# CH32F203C8T6-R1.net
KiCad netlist of a schematic drawn in Altium Designer
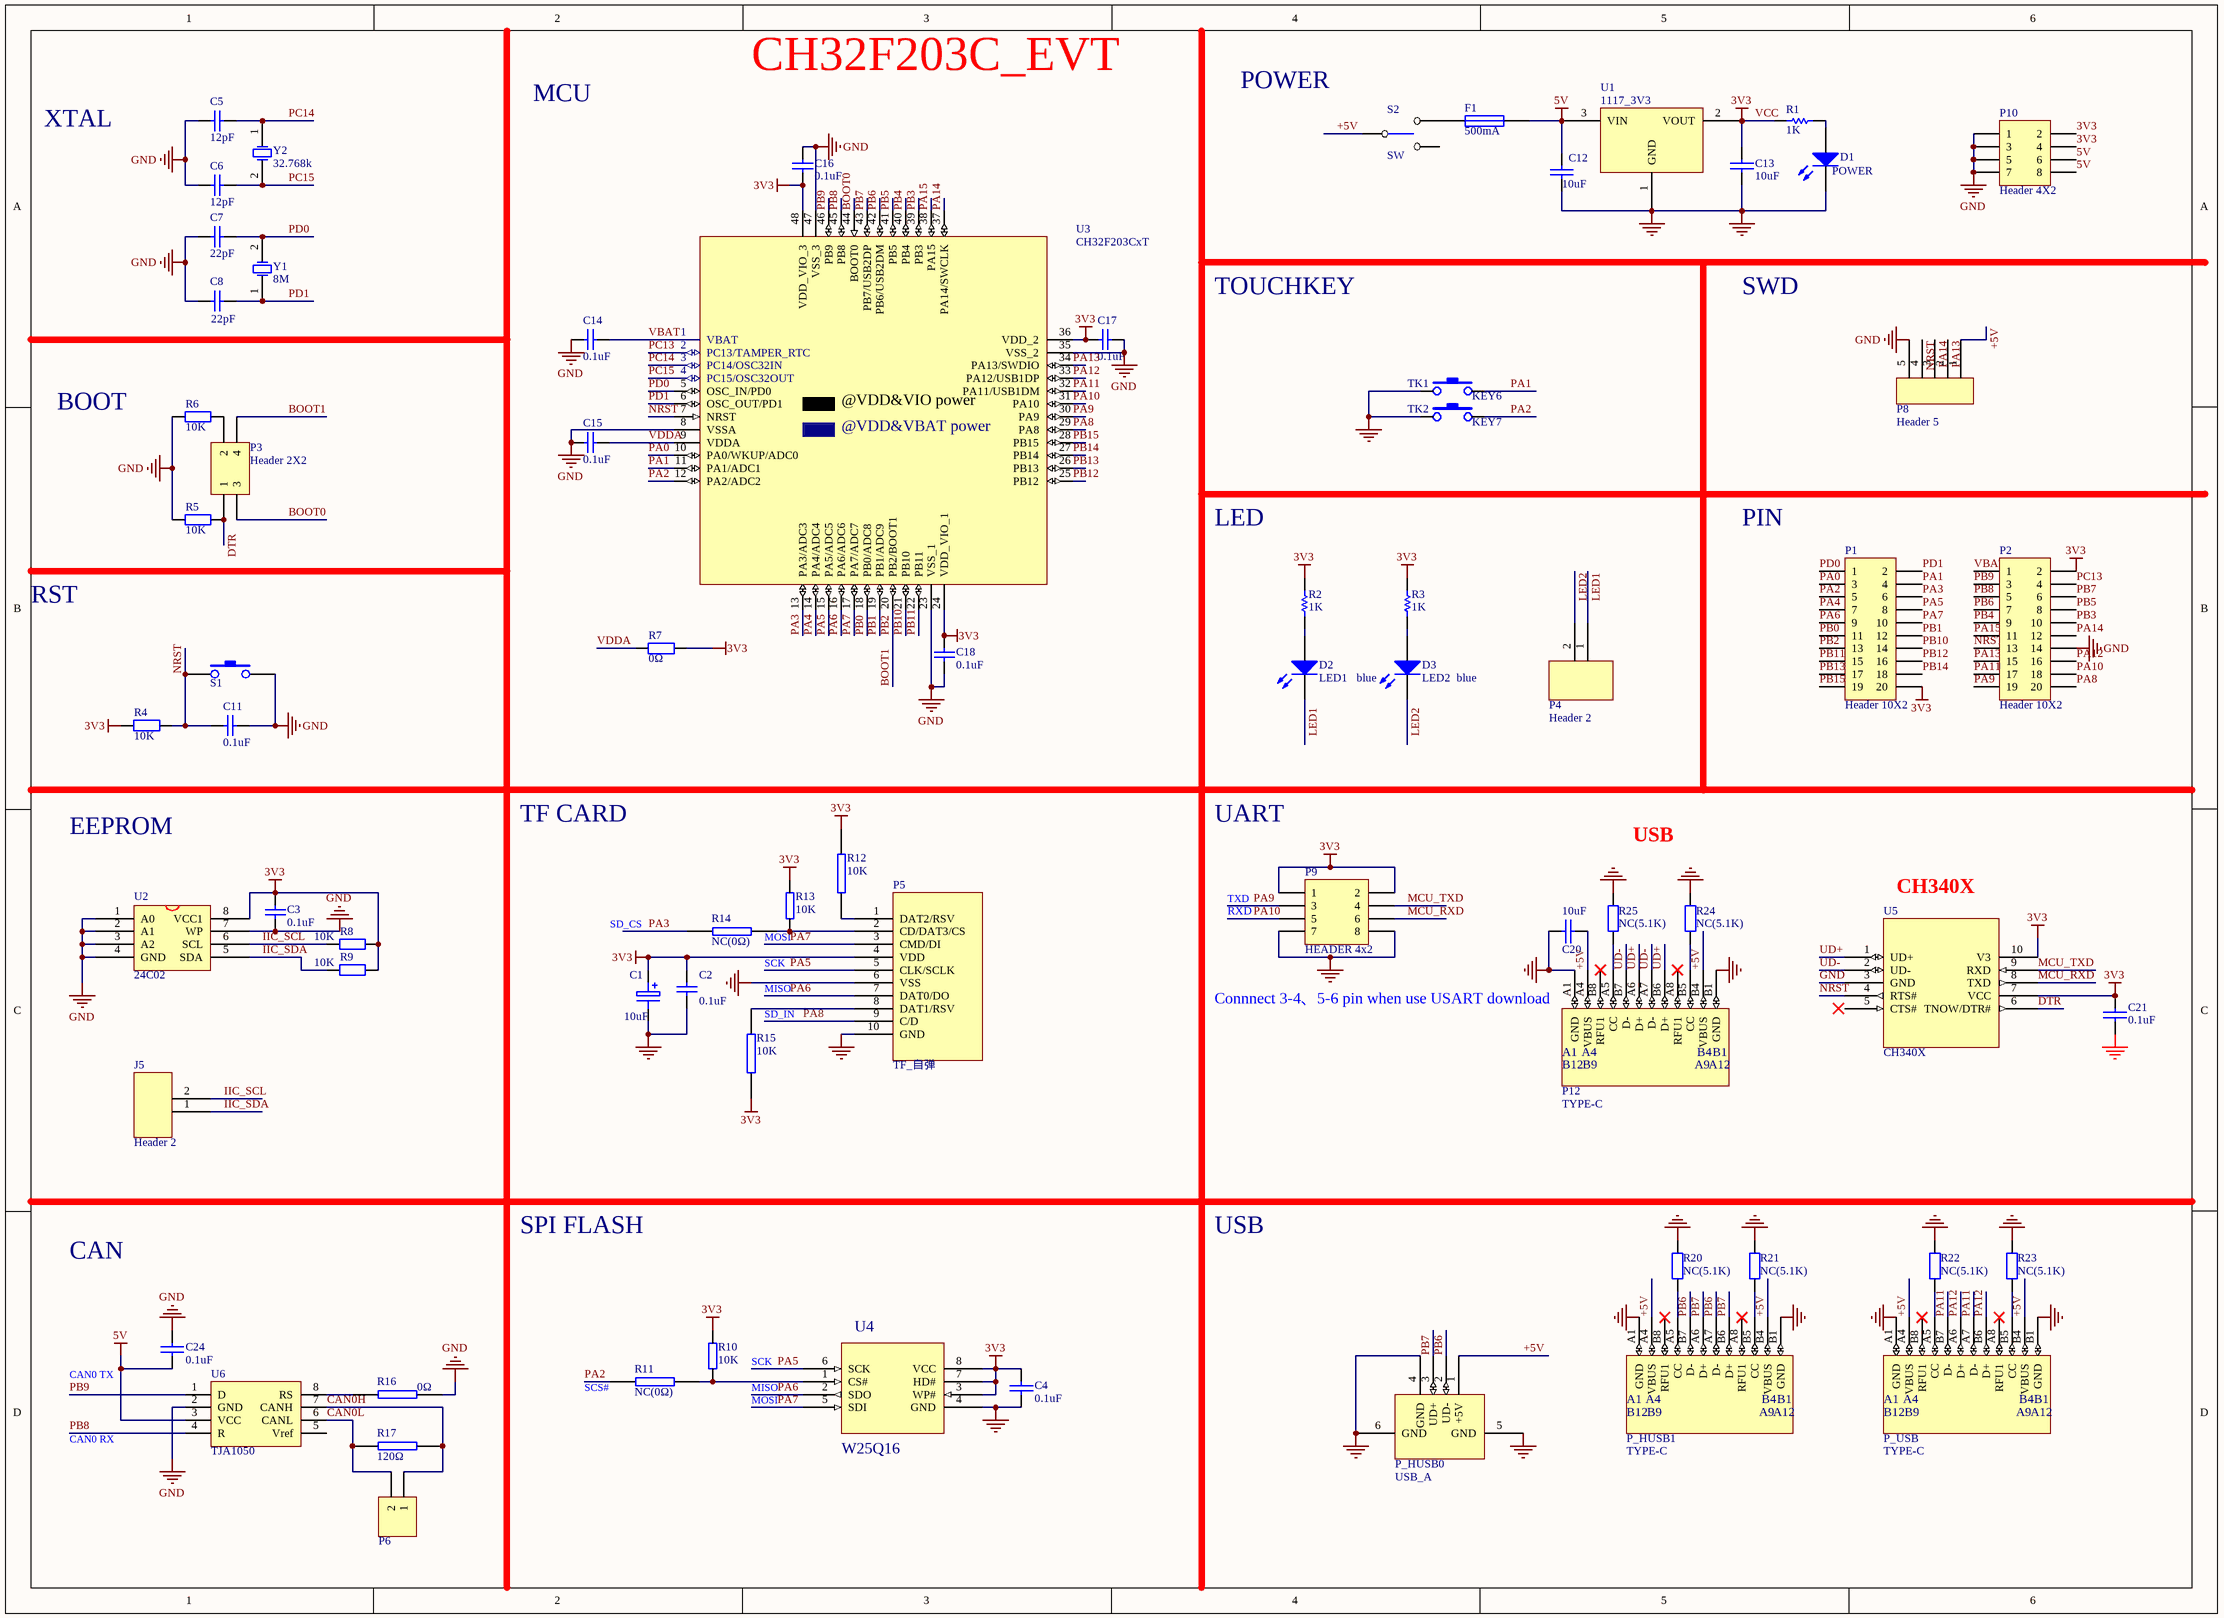
[diagram p0: CH32F203C8T6-R1.SchDoc]

(export (version "E")
  (design (tool "Eeschema 10.0.6"))
  (components
    (comp (ref "C1")
      (value "10uF")
      (footprint "3216")
      (description "Electrolytic Capacitor")
      (libsource (lib "*") (part "ELECTRO1"))
    )
    (comp (ref "C2")
      (value "0.1uF")
      (footprint "0603")
      (description "Capacitor")
      (fields (field (name "PUBLISHER") "Altium Limited"))
      (libsource (lib "*") (part "Cap"))
    )
    (comp (ref "C3")
      (value "0.1uF")
      (footprint "0603")
      (description "Capacitor")
      (fields (field (name "PUBLISHER") "Altium Limited"))
      (libsource (lib "Miscellaneous Devices") (part "Cap"))
    )
    (comp (ref "C4")
      (value "0.1uF")
      (footprint "0603")
      (description "Capacitor")
      (libsource (lib "") (part "CAP_1"))
    )
    (comp (ref "C5")
      (value "12pF")
      (footprint "0603")
      (description "Capacitor")
      (fields (field (name "PUBLISHER") "Altium Limited"))
      (libsource (lib "Miscellaneous Devices") (part "Cap"))
    )
    (comp (ref "C6")
      (value "12pF")
      (footprint "0603")
      (description "Capacitor")
      (fields (field (name "PUBLISHER") "Altium Limited"))
      (libsource (lib "Miscellaneous Devices") (part "Cap"))
    )
    (comp (ref "C7")
      (value "22pF")
      (footprint "0603")
      (description "Capacitor")
      (fields (field (name "PUBLISHER") "Altium Limited"))
      (libsource (lib "Miscellaneous Devices") (part "Cap"))
    )
    (comp (ref "C8")
      (value "22pF")
      (footprint "0603")
      (description "Capacitor")
      (fields (field (name "PUBLISHER") "Altium Limited"))
      (libsource (lib "Miscellaneous Devices") (part "Cap"))
    )
    (comp (ref "C11")
      (value "0.1uF")
      (footprint "0603")
      (description "Capacitor")
      (fields (field (name "PUBLISHER") "Altium Limited"))
      (libsource (lib "Miscellaneous Devices") (part "Cap"))
    )
    (comp (ref "C12")
      (value "10uF")
      (footprint "3216")
      (description "Capacitor")
      (libsource (lib "*") (part "CAP"))
    )
    (comp (ref "C13")
      (value "10uF")
      (footprint "0603")
      (description "Capacitor")
      (libsource (lib "*") (part "CAP"))
    )
    (comp (ref "C14")
      (value "0.1uF")
      (footprint "0603")
      (description "Capacitor")
      (fields (field (name "PUBLISHER") "Altium Limited"))
      (libsource (lib "Miscellaneous Devices") (part "Cap"))
    )
    (comp (ref "C15")
      (value "0.1uF")
      (footprint "0603")
      (description "Capacitor")
      (fields (field (name "PUBLISHER") "Altium Limited"))
      (libsource (lib "Miscellaneous Devices") (part "Cap"))
    )
    (comp (ref "C16")
      (value "0.1uF")
      (footprint "0603")
      (description "Capacitor")
      (fields (field (name "PUBLISHER") "Altium Limited"))
      (libsource (lib "Miscellaneous Devices") (part "Cap"))
    )
    (comp (ref "C17")
      (value "0.1uF")
      (footprint "0603")
      (description "Capacitor")
      (fields (field (name "PUBLISHER") "Altium Limited"))
      (libsource (lib "Miscellaneous Devices") (part "Cap"))
    )
    (comp (ref "C18")
      (value "0.1uF")
      (footprint "0603")
      (description "Capacitor")
      (fields (field (name "PUBLISHER") "Altium Limited"))
      (libsource (lib "Miscellaneous Devices") (part "Cap"))
    )
    (comp (ref "C20")
      (value "10uF")
      (footprint "3216_C")
      (description "Capacitor")
      (libsource (lib "*") (part "CAP"))
    )
    (comp (ref "C21")
      (value "0.1uF")
      (footprint "0603_C")
      (description "Capacitor")
      (libsource (lib "*") (part "CAP"))
    )
    (comp (ref "C24")
      (value "0.1uF")
      (footprint "0603")
      (description "Capacitor")
      (libsource (lib "") (part "CAP_1"))
    )
    (comp (ref "D1")
      (value "POWER")
      (footprint "0603L")
      (description "Typical INFRARED GaAs LED")
      (fields (field (name "PUBLISHER") "Altium Limited"))
      (libsource (lib "Miscellaneous Devices") (part "LED0"))
    )
    (comp (ref "D2")
      (value "LED1   blue")
      (footprint "0603L")
      (description "Typical INFRARED GaAs LED")
      (fields (field (name "PUBLISHER") "Altium Limited"))
      (libsource (lib "Miscellaneous Devices") (part "LED0"))
    )
    (comp (ref "D3")
      (value "LED2  blue")
      (footprint "0603L")
      (description "Typical INFRARED GaAs LED")
      (fields (field (name "PUBLISHER") "Altium Limited"))
      (libsource (lib "Miscellaneous Devices") (part "LED0"))
    )
    (comp (ref "F1")
      (value "500mA")
      (footprint "0603")
      (description "Fuse")
      (libsource (lib "*") (part "FUSE1"))
    )
    (comp (ref "J5") (value "Header 2") (footprint "SIP2 - 40mil") (libsource (lib "MYSCH") (part "2HEAD")))
    (comp (ref "P1")
      (value "Header 10X2")
      (footprint "IDC20")
      (description "Header, 10-Pin, Dual row")
      (fields (field (name "PUBLISHER") "Altium Limited"))
      (libsource (lib "Miscellaneous Connectors") (part "Header 10X2"))
    )
    (comp (ref "P2")
      (value "Header 10X2")
      (footprint "IDC20")
      (description "Header, 10-Pin, Dual row")
      (fields (field (name "PUBLISHER") "Altium Limited"))
      (libsource (lib "Miscellaneous Connectors") (part "Header 10X2"))
    )
    (comp (ref "P3")
      (value "Header 2X2")
      (footprint "HDR2X2")
      (description "Header, 2-Pin, Dual row")
      (fields (field (name "PUBLISHER") "Altium Limited"))
      (libsource (lib "Miscellaneous Connectors") (part "Header 2X2"))
    )
    (comp (ref "P4") (value "Header 2") (footprint "SIP2 - 40mil") (libsource (lib "") (part "2HEAD_1")))
    (comp (ref "P5") (value "TF_自弹") (footprint "TF_CARD") (libsource (lib "*") (part "TF_自弹")))
    (comp (ref "P6")
      (value "Header 2")
      (footprint "PORT2 4.5MM")
      (description "Header, 2-Pin")
      (fields (field (name "PUBLISHER") "Altium Limited"))
      (libsource (lib "Miscellaneous Connectors") (part "Header 2"))
    )
    (comp (ref "P8")
      (value "Header 5")
      (footprint "SIP5 - 40mil")
      (libsource (lib "PCB_Project1") (part "2HEAD"))
    )
    (comp (ref "P9")
      (value "HEADER 4x2")
      (footprint "MYPCB:IDC8-2.54mm")
      (description "Header, 4-Pin, Dual row")
      (libsource (lib "wch_sch_others") (part "HEADER 4x2"))
    )
    (comp (ref "P10")
      (value "Header 4X2")
      (footprint "IDC8")
      (description "Header, 4-Pin, Dual row")
      (fields (field (name "PUBLISHER") "Altium Limited"))
      (libsource (lib "Miscellaneous Connectors") (part "Header 4X2"))
    )
    (comp (ref "P12")
      (value "TYPE-C")
      (footprint "TYPE-C-Receptacle-2.0")
      (libsource (lib "*") (part "TYPE-C1"))
    )
    (comp (ref "P_HUSB0")
      (value "USB_A")
      (footprint "USBA-l")
      (description "USB Port")
      (libsource (lib "CHXXXSCH") (part "USB"))
    )
    (comp (ref "P_HUSB1")
      (value "TYPE-C")
      (footprint "TYPE-C-Receptacle-2.0")
      (libsource (lib "*") (part "TYPE-C1"))
    )
    (comp (ref "P_USB")
      (value "TYPE-C")
      (footprint "TYPE-C-Receptacle-2.0")
      (libsource (lib "*") (part "TYPE-C1"))
    )
    (comp (ref "R1")
      (value "1K")
      (footprint "0603")
      (description "Semiconductor Resistor")
      (fields (field (name "PUBLISHER") "Altium Limited"))
      (libsource (lib "Miscellaneous Devices") (part "Res Semi"))
    )
    (comp (ref "R2")
      (value "1K")
      (footprint "0603")
      (description "Semiconductor Resistor")
      (fields (field (name "PUBLISHER") "Altium Limited"))
      (libsource (lib "Miscellaneous Devices") (part "Res Semi"))
    )
    (comp (ref "R3")
      (value "1K")
      (footprint "0603")
      (description "Semiconductor Resistor")
      (fields (field (name "PUBLISHER") "Altium Limited"))
      (libsource (lib "Miscellaneous Devices") (part "Res Semi"))
    )
    (comp (ref "R4")
      (value "10K")
      (footprint "0603")
      (description "Resistor")
      (fields (field (name "PUBLISHER") "Altium Limited"))
      (libsource (lib "") (part "Res2_1"))
    )
    (comp (ref "R5")
      (value "10K")
      (footprint "0603")
      (description "Resistor")
      (fields (field (name "PUBLISHER") "Altium Limited"))
      (libsource (lib "") (part "Res2_1"))
    )
    (comp (ref "R6")
      (value "10K")
      (footprint "0603")
      (description "Resistor")
      (fields (field (name "PUBLISHER") "Altium Limited"))
      (libsource (lib "") (part "Res2_1"))
    )
    (comp (ref "R7")
      (value "0Ω")
      (footprint "0603")
      (description "Resistor")
      (fields (field (name "PUBLISHER") "Altium Limited"))
      (libsource (lib "") (part "Res2_1"))
    )
    (comp (ref "R8")
      (value "10K")
      (footprint "0603")
      (description "Resistor")
      (fields (field (name "PUBLISHER") "Altium Limited"))
      (libsource (lib "") (part "Res2_1"))
    )
    (comp (ref "R9")
      (value "10K")
      (footprint "0603")
      (description "Resistor")
      (fields (field (name "PUBLISHER") "Altium Limited"))
      (libsource (lib "") (part "Res2_1"))
    )
    (comp (ref "R10") (value "10K") (footprint "0603") (libsource (lib "*") (part "DZ")))
    (comp (ref "R11") (value "NC(0Ω)") (footprint "0603") (libsource (lib "*") (part "RES2")))
    (comp (ref "R12") (value "10K") (footprint "0603") (libsource (lib "*") (part "RES2")))
    (comp (ref "R13") (value "10K") (footprint "0603") (libsource (lib "*") (part "DZ")))
    (comp (ref "R14") (value "NC(0Ω)") (footprint "0603") (libsource (lib "*") (part "RES2")))
    (comp (ref "R15") (value "10K") (footprint "0603") (libsource (lib "*") (part "RES2")))
    (comp (ref "R16") (value "0Ω") (footprint "0603") (libsource (lib "*") (part "RES2")))
    (comp (ref "R17") (value "120Ω") (footprint "0603") (libsource (lib "*") (part "RES2")))
    (comp (ref "R20")
      (value "NC(5.1K)")
      (footprint "0603")
      (description "Resistor")
      (libsource (lib "Miscellaneous Devices") (part "Res2"))
    )
    (comp (ref "R21")
      (value "NC(5.1K)")
      (footprint "0603")
      (description "Resistor")
      (libsource (lib "Miscellaneous Devices") (part "Res2"))
    )
    (comp (ref "R22")
      (value "NC(5.1K)")
      (footprint "0603")
      (description "Resistor")
      (libsource (lib "Miscellaneous Devices") (part "Res2"))
    )
    (comp (ref "R23")
      (value "NC(5.1K)")
      (footprint "0603")
      (description "Resistor")
      (libsource (lib "Miscellaneous Devices") (part "Res2"))
    )
    (comp (ref "R24")
      (value "NC(5.1K)")
      (footprint "0603")
      (description "Resistor")
      (libsource (lib "Miscellaneous Devices") (part "Res2"))
    )
    (comp (ref "R25")
      (value "NC(5.1K)")
      (footprint "0603")
      (description "Resistor")
      (libsource (lib "Miscellaneous Devices") (part "Res2"))
    )
    (comp (ref "S1") (value "KEY") (footprint "贴片按键") (libsource (lib "CCDXPLIB") (part "KEY")))
    (comp (ref "S2") (value "SW") (footprint "KEY2") (libsource (lib "MYSCH") (part "SW")))
    (comp (ref "TK1") (value "KEY6") (footprint "KEY68") (libsource (lib "*") (part "KEY")))
    (comp (ref "TK2") (value "KEY7") (footprint "KEY68") (libsource (lib "*") (part "KEY")))
    (comp (ref "U1") (value "1117_3V3") (footprint "SOT-223") (libsource (lib "*") (part "LM1117_3.3V")))
    (comp (ref "U2") (value "24C02") (footprint "SOP8") (libsource (lib "Elite_SCH") (part "24C256")))
    (comp (ref "U3")
      (value "CH32F203CxT")
      (footprint "LQFP48")
      (description "ARM M3 LMD-MCU, 144MHz, 2*USB FS, CAN")
      (libsource (lib "CHXXX") (part "CH32F203CxT"))
    )
    (comp (ref "U4")
      (value "W25Q16")
      (footprint "016 SO-8")
      (libsource (lib "*") (part "Pro89C.tmp_25F512_2"))
    )
    (comp (ref "U5")
      (value "CH340X")
      (footprint "MSOP10")
      (description "USB to TTL Serial / UART")
      (libsource (lib "CHXXX") (part "CH340X"))
    )
    (comp (ref "U6") (value "TJA1050") (footprint "SOP8") (libsource (lib "CAN") (part "Component_1")))
    (comp (ref "Y1")
      (value "8M")
      (footprint "XT62/28")
      (description "Crystal Oscillator")
      (fields (field (name "PUBLISHER") "Altium Limited"))
      (libsource (lib "Miscellaneous Devices") (part "XTAL"))
    )
    (comp (ref "Y2")
      (value "32.768k")
      (footprint "FC-135")
      (description "Crystal Oscillator")
      (fields (field (name "PUBLISHER") "Altium Limited"))
      (libsource (lib "Miscellaneous Devices") (part "XTAL"))
    )
  )
  (nets
    (net (code "1") (name "/+5V") (class "Default")
      (node (ref "C20") (pin "2") (pinfunction "2_2") (pintype "passive"))
      (node (ref "P12") (pin "A4") (pinfunction "VBUS_A4") (pintype "bidirectional"))
      (node (ref "P12") (pin "B4") (pinfunction "VBUS_B4") (pintype "bidirectional"))
      (node (ref "P8") (pin "1") (pintype "passive"))
      (node (ref "P_HUSB0") (pin "1") (pinfunction "+5V_1") (pintype "power_in"))
      (node (ref "P_HUSB1") (pin "A4") (pinfunction "VBUS_A4") (pintype "bidirectional"))
      (node (ref "P_HUSB1") (pin "B4") (pinfunction "VBUS_B4") (pintype "bidirectional"))
      (node (ref "P_USB") (pin "A4") (pinfunction "VBUS_A4") (pintype "bidirectional"))
      (node (ref "P_USB") (pin "B4") (pinfunction "VBUS_B4") (pintype "bidirectional"))
      (node (ref "S2") (pin "1") (pinfunction "1_1") (pintype "passive"))
    )
    (net (code "3") (name "/BOOT0") (class "Default")
      (node (ref "P3") (pin "3") (pinfunction "3_3") (pintype "passive"))
      (node (ref "U3") (pin "44") (pinfunction "BOOT0_44") (pintype "input"))
    )
    (net (code "4") (name "/BOOT1") (class "Default")
      (node (ref "P1") (pin "13") (pinfunction "13_13") (pintype "passive"))
      (node (ref "P3") (pin "4") (pinfunction "4_4") (pintype "passive"))
      (node (ref "U3") (pin "20") (pinfunction "PB2/BOOT1_20") (pintype "bidirectional"))
    )
    (net (code "5") (name "/CAN0H") (class "Default")
      (node (ref "P6") (pin "1") (pinfunction "1_1") (pintype "passive"))
      (node (ref "R17") (pin "1") (pinfunction "1_1") (pintype "passive"))
      (node (ref "U6") (pin "7") (pinfunction "CANH_7") (pintype "passive"))
    )
    (net (code "6") (name "/CAN0L") (class "Default")
      (node (ref "P6") (pin "2") (pinfunction "2_2") (pintype "passive"))
      (node (ref "R17") (pin "2") (pinfunction "2_2") (pintype "passive"))
      (node (ref "U6") (pin "6") (pinfunction "CANL_6") (pintype "passive"))
    )
    (net (code "7") (name "/DTR") (class "Default")
      (node (ref "P3") (pin "1") (pinfunction "1_1") (pintype "passive"))
      (node (ref "R5") (pin "1") (pinfunction "1_1") (pintype "passive"))
      (node (ref "U5") (pin "6") (pinfunction "TNOW/DTR#_6") (pintype "output"))
    )
    (net (code "8") (name "/IIC_SCL") (class "Default")
      (node (ref "J5") (pin "2") (pintype "passive"))
      (node (ref "R8") (pin "2") (pinfunction "2_2") (pintype "passive"))
      (node (ref "U2") (pin "6") (pinfunction "SCL_6") (pintype "passive"))
    )
    (net (code "9") (name "/IIC_SDA") (class "Default")
      (node (ref "J5") (pin "1") (pintype "passive"))
      (node (ref "R9") (pin "2") (pinfunction "2_2") (pintype "passive"))
      (node (ref "U2") (pin "5") (pinfunction "SDA_5") (pintype "passive"))
    )
    (net (code "10") (name "/LED1") (class "Default")
      (node (ref "D2") (pin "2") (pinfunction "K_2") (pintype "passive"))
      (node (ref "P4") (pin "1") (pintype "passive"))
    )
    (net (code "11") (name "/LED2") (class "Default")
      (node (ref "D3") (pin "2") (pinfunction "K_2") (pintype "passive"))
      (node (ref "P4") (pin "2") (pintype "passive"))
    )
    (net (code "12") (name "/MCU_RXD") (class "Default")
      (node (ref "P9") (pin "6") (pinfunction "6_6") (pintype "passive"))
      (node (ref "U5") (pin "8") (pinfunction "TXD_8") (pintype "output"))
    )
    (net (code "13") (name "/MCU_TXD") (class "Default")
      (node (ref "P9") (pin "4") (pinfunction "4_4") (pintype "passive"))
      (node (ref "U5") (pin "9") (pinfunction "RXD_9") (pintype "input"))
    )
    (net (code "14") (name "/NRST") (class "Default")
      (node (ref "C11") (pin "2") (pinfunction "2_2") (pintype "passive"))
      (node (ref "P2") (pin "13") (pinfunction "13_13") (pintype "passive"))
      (node (ref "P8") (pin "4") (pintype "passive"))
      (node (ref "R4") (pin "1") (pinfunction "1_1") (pintype "passive"))
      (node (ref "S1") (pin "1") (pinfunction "1_1") (pintype "passive"))
      (node (ref "U3") (pin "7") (pinfunction "NRST_7") (pintype "input"))
      (node (ref "U5") (pin "4") (pinfunction "RTS#_4") (pintype "output"))
    )
    (net (code "15") (name "/PA0") (class "Default")
      (node (ref "P1") (pin "3") (pinfunction "3_3") (pintype "passive"))
      (node (ref "U3") (pin "10") (pinfunction "PA0/WKUP/ADC0_10") (pintype "bidirectional"))
    )
    (net (code "16") (name "/PA1") (class "Default")
      (node (ref "P1") (pin "4") (pinfunction "4_4") (pintype "passive"))
      (node (ref "TK1") (pin "1") (pintype "passive"))
      (node (ref "U3") (pin "11") (pinfunction "PA1/ADC1_11") (pintype "bidirectional"))
    )
    (net (code "17") (name "/PA2") (class "Default")
      (node (ref "P1") (pin "5") (pinfunction "5_5") (pintype "passive"))
      (node (ref "R11") (pin "2") (pinfunction "2_2") (pintype "passive"))
      (node (ref "TK2") (pin "1") (pintype "passive"))
      (node (ref "U3") (pin "12") (pinfunction "PA2/ADC2_12") (pintype "bidirectional"))
    )
    (net (code "18") (name "/PA3") (class "Default")
      (node (ref "P1") (pin "6") (pinfunction "6_6") (pintype "passive"))
      (node (ref "R14") (pin "2") (pinfunction "2_2") (pintype "passive"))
      (node (ref "U3") (pin "13") (pinfunction "PA3/ADC3_13") (pintype "bidirectional"))
    )
    (net (code "19") (name "/PA4") (class "Default")
      (node (ref "P1") (pin "7") (pinfunction "7_7") (pintype "passive"))
      (node (ref "U3") (pin "14") (pinfunction "PA4/ADC4_14") (pintype "bidirectional"))
    )
    (net (code "20") (name "/PA5") (class "Default")
      (node (ref "P1") (pin "8") (pinfunction "8_8") (pintype "passive"))
      (node (ref "P5") (pin "5") (pinfunction "CLK/SCLK_5") (pintype "passive"))
      (node (ref "U3") (pin "15") (pinfunction "PA5/ADC5_15") (pintype "bidirectional"))
      (node (ref "U4") (pin "6") (pinfunction "SCK_6") (pintype "input"))
    )
    (net (code "21") (name "/PA6") (class "Default")
      (node (ref "P1") (pin "9") (pinfunction "9_9") (pintype "passive"))
      (node (ref "P5") (pin "7") (pinfunction "DAT0/DO_7") (pintype "passive"))
      (node (ref "U3") (pin "16") (pinfunction "PA6/ADC6_16") (pintype "bidirectional"))
      (node (ref "U4") (pin "2") (pinfunction "SDO_2") (pintype "output"))
    )
    (net (code "22") (name "/PA7") (class "Default")
      (node (ref "P1") (pin "10") (pinfunction "10_10") (pintype "passive"))
      (node (ref "P5") (pin "3") (pinfunction "CMD/DI_3") (pintype "passive"))
      (node (ref "U3") (pin "17") (pinfunction "PA7/ADC7_17") (pintype "bidirectional"))
      (node (ref "U4") (pin "5") (pinfunction "SDI_5") (pintype "input"))
    )
    (net (code "23") (name "/PA8") (class "Default")
      (node (ref "P2") (pin "20") (pinfunction "20_20") (pintype "passive"))
      (node (ref "P5") (pin "9") (pinfunction "C/D_9") (pintype "passive"))
      (node (ref "U3") (pin "29") (pinfunction "PA8_29") (pintype "bidirectional"))
    )
    (net (code "24") (name "/PA9") (class "Default")
      (node (ref "P2") (pin "19") (pinfunction "19_19") (pintype "passive"))
      (node (ref "P9") (pin "3") (pinfunction "3_3") (pintype "passive"))
      (node (ref "U3") (pin "30") (pinfunction "PA9_30") (pintype "bidirectional"))
    )
    (net (code "25") (name "/PA10") (class "Default")
      (node (ref "P2") (pin "18") (pinfunction "18_18") (pintype "passive"))
      (node (ref "P9") (pin "5") (pinfunction "5_5") (pintype "passive"))
      (node (ref "U3") (pin "31") (pinfunction "PA10_31") (pintype "bidirectional"))
    )
    (net (code "26") (name "/PA11") (class "Default")
      (node (ref "P2") (pin "17") (pinfunction "17_17") (pintype "passive"))
      (node (ref "P_USB") (pin "A7") (pinfunction "D-_A7") (pintype "bidirectional"))
      (node (ref "P_USB") (pin "B7") (pinfunction "D-_B7") (pintype "bidirectional"))
      (node (ref "U3") (pin "32") (pinfunction "PA11/USB1DM_32") (pintype "bidirectional"))
    )
    (net (code "27") (name "/PA12") (class "Default")
      (node (ref "P2") (pin "16") (pinfunction "16_16") (pintype "passive"))
      (node (ref "P_USB") (pin "A6") (pinfunction "D+_A6") (pintype "bidirectional"))
      (node (ref "P_USB") (pin "B6") (pinfunction "D+_B6") (pintype "bidirectional"))
      (node (ref "U3") (pin "33") (pinfunction "PA12/USB1DP_33") (pintype "bidirectional"))
    )
    (net (code "28") (name "/PA13") (class "Default")
      (node (ref "P2") (pin "15") (pinfunction "15_15") (pintype "passive"))
      (node (ref "P8") (pin "2") (pintype "passive"))
      (node (ref "U3") (pin "34") (pinfunction "PA13/SWDIO_34") (pintype "bidirectional"))
    )
    (net (code "29") (name "/PA14") (class "Default")
      (node (ref "P2") (pin "12") (pinfunction "12_12") (pintype "passive"))
      (node (ref "P8") (pin "3") (pintype "passive"))
      (node (ref "U3") (pin "37") (pinfunction "PA14/SWCLK_37") (pintype "bidirectional"))
    )
    (net (code "30") (name "/PA15") (class "Default")
      (node (ref "P2") (pin "11") (pinfunction "11_11") (pintype "passive"))
      (node (ref "U3") (pin "38") (pinfunction "PA15_38") (pintype "bidirectional"))
    )
    (net (code "31") (name "/PB0") (class "Default")
      (node (ref "P1") (pin "11") (pinfunction "11_11") (pintype "passive"))
      (node (ref "U3") (pin "18") (pinfunction "PB0/ADC8_18") (pintype "bidirectional"))
    )
    (net (code "32") (name "/PB1") (class "Default")
      (node (ref "P1") (pin "12") (pinfunction "12_12") (pintype "passive"))
      (node (ref "U3") (pin "19") (pinfunction "PB1/ADC9_19") (pintype "bidirectional"))
    )
    (net (code "33") (name "/PB3") (class "Default")
      (node (ref "P2") (pin "10") (pinfunction "10_10") (pintype "passive"))
      (node (ref "U3") (pin "39") (pinfunction "PB3_39") (pintype "bidirectional"))
    )
    (net (code "34") (name "/PB4") (class "Default")
      (node (ref "P2") (pin "9") (pinfunction "9_9") (pintype "passive"))
      (node (ref "U3") (pin "40") (pinfunction "PB4_40") (pintype "bidirectional"))
    )
    (net (code "35") (name "/PB5") (class "Default")
      (node (ref "P2") (pin "8") (pinfunction "8_8") (pintype "passive"))
      (node (ref "U3") (pin "41") (pinfunction "PB5_41") (pintype "bidirectional"))
    )
    (net (code "36") (name "/PB6") (class "Default")
      (node (ref "P2") (pin "7") (pinfunction "7_7") (pintype "passive"))
      (node (ref "P_HUSB0") (pin "2") (pinfunction "UD-_2") (pintype "bidirectional"))
      (node (ref "P_HUSB1") (pin "A7") (pinfunction "D-_A7") (pintype "bidirectional"))
      (node (ref "P_HUSB1") (pin "B7") (pinfunction "D-_B7") (pintype "bidirectional"))
      (node (ref "U3") (pin "42") (pinfunction "PB6/USB2DM_42") (pintype "bidirectional"))
    )
    (net (code "37") (name "/PB7") (class "Default")
      (node (ref "P2") (pin "6") (pinfunction "6_6") (pintype "passive"))
      (node (ref "P_HUSB0") (pin "3") (pinfunction "UD+_3") (pintype "bidirectional"))
      (node (ref "P_HUSB1") (pin "A6") (pinfunction "D+_A6") (pintype "bidirectional"))
      (node (ref "P_HUSB1") (pin "B6") (pinfunction "D+_B6") (pintype "bidirectional"))
      (node (ref "U3") (pin "43") (pinfunction "PB7/USB2DP_43") (pintype "bidirectional"))
    )
    (net (code "38") (name "/PB8") (class "Default")
      (node (ref "P2") (pin "5") (pinfunction "5_5") (pintype "passive"))
      (node (ref "U3") (pin "45") (pinfunction "PB8_45") (pintype "bidirectional"))
      (node (ref "U6") (pin "4") (pinfunction "R_4") (pintype "passive"))
    )
    (net (code "39") (name "/PB9") (class "Default")
      (node (ref "P2") (pin "3") (pinfunction "3_3") (pintype "passive"))
      (node (ref "U3") (pin "46") (pinfunction "PB9_46") (pintype "bidirectional"))
      (node (ref "U6") (pin "1") (pinfunction "D_1") (pintype "passive"))
    )
    (net (code "40") (name "/PB10") (class "Default")
      (node (ref "P1") (pin "14") (pinfunction "14_14") (pintype "passive"))
      (node (ref "U3") (pin "21") (pinfunction "PB10_21") (pintype "bidirectional"))
    )
    (net (code "41") (name "/PB11") (class "Default")
      (node (ref "P1") (pin "15") (pinfunction "15_15") (pintype "passive"))
      (node (ref "U3") (pin "22") (pinfunction "PB11_22") (pintype "bidirectional"))
    )
    (net (code "42") (name "/PB12") (class "Default")
      (node (ref "P1") (pin "16") (pinfunction "16_16") (pintype "passive"))
      (node (ref "U3") (pin "25") (pinfunction "PB12_25") (pintype "bidirectional"))
    )
    (net (code "43") (name "/PB13") (class "Default")
      (node (ref "P1") (pin "17") (pinfunction "17_17") (pintype "passive"))
      (node (ref "U3") (pin "26") (pinfunction "PB13_26") (pintype "bidirectional"))
    )
    (net (code "44") (name "/PB14") (class "Default")
      (node (ref "P1") (pin "18") (pinfunction "18_18") (pintype "passive"))
      (node (ref "U3") (pin "27") (pinfunction "PB14_27") (pintype "bidirectional"))
    )
    (net (code "45") (name "/PB15") (class "Default")
      (node (ref "P1") (pin "19") (pinfunction "19_19") (pintype "passive"))
      (node (ref "U3") (pin "28") (pinfunction "PB15_28") (pintype "bidirectional"))
    )
    (net (code "46") (name "/PC13") (class "Default")
      (node (ref "P2") (pin "4") (pinfunction "4_4") (pintype "passive"))
      (node (ref "U3") (pin "2") (pinfunction "PC13/TAMPER_RTC_2") (pintype "bidirectional"))
    )
    (net (code "47") (name "/PC14") (class "Default")
      (node (ref "C5") (pin "1") (pinfunction "1_1") (pintype "passive"))
      (node (ref "U3") (pin "3") (pinfunction "PC14/OSC32IN_3") (pintype "bidirectional"))
      (node (ref "Y2") (pin "1") (pinfunction "OSC1_1") (pintype "passive"))
    )
    (net (code "48") (name "/PC15") (class "Default")
      (node (ref "C6") (pin "1") (pinfunction "1_1") (pintype "passive"))
      (node (ref "U3") (pin "4") (pinfunction "PC15/OSC32OUT_4") (pintype "bidirectional"))
      (node (ref "Y2") (pin "2") (pinfunction "OSC2_2") (pintype "passive"))
    )
    (net (code "49") (name "/PD0") (class "Default")
      (node (ref "C7") (pin "2") (pinfunction "2_2") (pintype "passive"))
      (node (ref "P1") (pin "1") (pinfunction "1_1") (pintype "passive"))
      (node (ref "U3") (pin "5") (pinfunction "OSC_IN/PD0_5") (pintype "bidirectional"))
      (node (ref "Y1") (pin "2") (pinfunction "OSC2_2") (pintype "passive"))
    )
    (net (code "50") (name "/PD1") (class "Default")
      (node (ref "C8") (pin "2") (pinfunction "2_2") (pintype "passive"))
      (node (ref "P1") (pin "2") (pinfunction "2_2") (pintype "passive"))
      (node (ref "U3") (pin "6") (pinfunction "OSC_OUT/PD1_6") (pintype "bidirectional"))
      (node (ref "Y1") (pin "1") (pinfunction "OSC1_1") (pintype "passive"))
    )
    (net (code "51") (name "/UD+") (class "Default")
      (node (ref "P12") (pin "A6") (pinfunction "D+_A6") (pintype "bidirectional"))
      (node (ref "P12") (pin "B6") (pinfunction "D+_B6") (pintype "bidirectional"))
      (node (ref "U5") (pin "1") (pinfunction "UD+_1") (pintype "bidirectional"))
    )
    (net (code "52") (name "/UD-") (class "Default")
      (node (ref "P12") (pin "A7") (pinfunction "D-_A7") (pintype "bidirectional"))
      (node (ref "P12") (pin "B7") (pinfunction "D-_B7") (pintype "bidirectional"))
      (node (ref "U5") (pin "2") (pinfunction "UD-_2") (pintype "bidirectional"))
    )
    (net (code "53") (name "/VBAT") (class "Default")
      (node (ref "C14") (pin "1") (pinfunction "1_1") (pintype "passive"))
      (node (ref "P2") (pin "1") (pinfunction "1_1") (pintype "passive"))
      (node (ref "U3") (pin "1") (pinfunction "VBAT_1") (pintype "power_in"))
    )
    (net (code "54") (name "/VDDA") (class "Default")
      (node (ref "C15") (pin "1") (pinfunction "1_1") (pintype "passive"))
      (node (ref "R7") (pin "2") (pinfunction "2_2") (pintype "passive"))
      (node (ref "U3") (pin "9") (pinfunction "VDDA_9") (pintype "power_in"))
    )
    (net (code "55") (name "3V3") (class "Default")
      (node (ref "C1") (pin "1") (pinfunction "1_1") (pintype "passive"))
      (node (ref "C13") (pin "1") (pinfunction "1_1") (pintype "passive"))
      (node (ref "C16") (pin "2") (pinfunction "2_2") (pintype "passive"))
      (node (ref "C17") (pin "2") (pinfunction "2_2") (pintype "passive"))
      (node (ref "C18") (pin "2") (pinfunction "2_2") (pintype "passive"))
      (node (ref "C2") (pin "1") (pinfunction "1_1") (pintype "passive"))
      (node (ref "C21") (pin "1") (pinfunction "1_1") (pintype "passive"))
      (node (ref "C3") (pin "2") (pinfunction "2_2") (pintype "passive"))
      (node (ref "C4") (pin "2") (pinfunction "2_2") (pintype "passive"))
      (node (ref "P1") (pin "20") (pinfunction "20_20") (pintype "passive"))
      (node (ref "P10") (pin "2") (pinfunction "2_2") (pintype "passive"))
      (node (ref "P10") (pin "4") (pinfunction "4_4") (pintype "passive"))
      (node (ref "P2") (pin "2") (pinfunction "2_2") (pintype "passive"))
      (node (ref "P5") (pin "4") (pinfunction "VDD_4") (pintype "passive"))
      (node (ref "P9") (pin "1") (pinfunction "1_1") (pintype "passive"))
      (node (ref "P9") (pin "2") (pinfunction "2_2") (pintype "passive"))
      (node (ref "R1") (pin "2") (pinfunction "2_2") (pintype "passive"))
      (node (ref "R10") (pin "2") (pintype "passive"))
      (node (ref "R12") (pin "2") (pinfunction "2_2") (pintype "passive"))
      (node (ref "R13") (pin "2") (pintype "passive"))
      (node (ref "R15") (pin "1") (pinfunction "1_1") (pintype "passive"))
      (node (ref "R2") (pin "1") (pinfunction "1_1") (pintype "passive"))
      (node (ref "R3") (pin "1") (pinfunction "1_1") (pintype "passive"))
      (node (ref "R4") (pin "2") (pinfunction "2_2") (pintype "passive"))
      (node (ref "R7") (pin "1") (pinfunction "1_1") (pintype "passive"))
      (node (ref "R8") (pin "1") (pinfunction "1_1") (pintype "passive"))
      (node (ref "R9") (pin "1") (pinfunction "1_1") (pintype "passive"))
      (node (ref "U1") (pin "2") (pinfunction "VOUT_2") (pintype "passive"))
      (node (ref "U2") (pin "8") (pinfunction "VCC1_8") (pintype "passive"))
      (node (ref "U3") (pin "24") (pinfunction "VDD_VIO_1_24") (pintype "power_in"))
      (node (ref "U3") (pin "36") (pinfunction "VDD_2_36") (pintype "power_in"))
      (node (ref "U3") (pin "48") (pinfunction "VDD_VIO_3_48") (pintype "power_in"))
      (node (ref "U4") (pin "3") (pinfunction "WP#_3") (pintype "input"))
      (node (ref "U4") (pin "7") (pinfunction "HD#_7") (pintype "power_in"))
      (node (ref "U4") (pin "8") (pinfunction "VCC_8") (pintype "power_in"))
      (node (ref "U5") (pin "10") (pinfunction "V3_10") (pintype "power_in"))
      (node (ref "U5") (pin "7") (pinfunction "VCC_7") (pintype "power_in"))
    )
    (net (code "56") (name "5V") (class "Default")
      (node (ref "C12") (pin "1") (pinfunction "1_1") (pintype "passive"))
      (node (ref "C24") (pin "2") (pinfunction "2_2") (pintype "passive"))
      (node (ref "F1") (pin "2") (pinfunction "2_2") (pintype "passive"))
      (node (ref "P10") (pin "6") (pinfunction "6_6") (pintype "passive"))
      (node (ref "P10") (pin "8") (pinfunction "8_8") (pintype "passive"))
      (node (ref "U1") (pin "3") (pinfunction "VIN_3") (pintype "passive"))
      (node (ref "U6") (pin "3") (pinfunction "VCC_3") (pintype "passive"))
    )
    (net (code "57") (name "GND") (class "Default")
      (node (ref "C1") (pin "2") (pinfunction "2_2") (pintype "passive"))
      (node (ref "C11") (pin "1") (pinfunction "1_1") (pintype "passive"))
      (node (ref "C12") (pin "2") (pinfunction "2_2") (pintype "passive"))
      (node (ref "C13") (pin "2") (pinfunction "2_2") (pintype "passive"))
      (node (ref "C14") (pin "2") (pinfunction "2_2") (pintype "passive"))
      (node (ref "C15") (pin "2") (pinfunction "2_2") (pintype "passive"))
      (node (ref "C16") (pin "1") (pinfunction "1_1") (pintype "passive"))
      (node (ref "C17") (pin "1") (pinfunction "1_1") (pintype "passive"))
      (node (ref "C18") (pin "1") (pinfunction "1_1") (pintype "passive"))
      (node (ref "C2") (pin "2") (pinfunction "2_2") (pintype "passive"))
      (node (ref "C20") (pin "1") (pinfunction "1_1") (pintype "passive"))
      (node (ref "C21") (pin "2") (pinfunction "2_2") (pintype "passive"))
      (node (ref "C24") (pin "1") (pinfunction "1_1") (pintype "passive"))
      (node (ref "C3") (pin "1") (pinfunction "1_1") (pintype "passive"))
      (node (ref "C4") (pin "1") (pinfunction "1_1") (pintype "passive"))
      (node (ref "C5") (pin "2") (pinfunction "2_2") (pintype "passive"))
      (node (ref "C6") (pin "2") (pinfunction "2_2") (pintype "passive"))
      (node (ref "C7") (pin "1") (pinfunction "1_1") (pintype "passive"))
      (node (ref "C8") (pin "1") (pinfunction "1_1") (pintype "passive"))
      (node (ref "D1") (pin "2") (pinfunction "K_2") (pintype "passive"))
      (node (ref "P10") (pin "1") (pinfunction "1_1") (pintype "passive"))
      (node (ref "P10") (pin "3") (pinfunction "3_3") (pintype "passive"))
      (node (ref "P10") (pin "5") (pinfunction "5_5") (pintype "passive"))
      (node (ref "P10") (pin "7") (pinfunction "7_7") (pintype "passive"))
      (node (ref "P12") (pin "A1") (pinfunction "GND_A1") (pintype "bidirectional"))
      (node (ref "P12") (pin "B1") (pinfunction "GND_B1") (pintype "bidirectional"))
      (node (ref "P2") (pin "14") (pinfunction "14_14") (pintype "passive"))
      (node (ref "P5") (pin "10") (pinfunction "GND_10") (pintype "passive"))
      (node (ref "P5") (pin "6") (pinfunction "VSS_6") (pintype "passive"))
      (node (ref "P8") (pin "5") (pintype "passive"))
      (node (ref "P9") (pin "7") (pinfunction "7_7") (pintype "passive"))
      (node (ref "P9") (pin "8") (pinfunction "8_8") (pintype "passive"))
      (node (ref "P_HUSB0") (pin "4") (pinfunction "GND_4") (pintype "power_in"))
      (node (ref "P_HUSB0") (pin "5") (pinfunction "GND_5") (pintype "power_in"))
      (node (ref "P_HUSB0") (pin "6") (pinfunction "GND_6") (pintype "power_in"))
      (node (ref "P_HUSB1") (pin "A1") (pinfunction "GND_A1") (pintype "bidirectional"))
      (node (ref "P_HUSB1") (pin "B1") (pinfunction "GND_B1") (pintype "bidirectional"))
      (node (ref "P_USB") (pin "A1") (pinfunction "GND_A1") (pintype "bidirectional"))
      (node (ref "P_USB") (pin "B1") (pinfunction "GND_B1") (pintype "bidirectional"))
      (node (ref "R16") (pin "1") (pinfunction "1_1") (pintype "passive"))
      (node (ref "R20") (pin "2") (pinfunction "2_2") (pintype "passive"))
      (node (ref "R21") (pin "2") (pinfunction "2_2") (pintype "passive"))
      (node (ref "R22") (pin "2") (pinfunction "2_2") (pintype "passive"))
      (node (ref "R23") (pin "2") (pinfunction "2_2") (pintype "passive"))
      (node (ref "R24") (pin "2") (pinfunction "2_2") (pintype "passive"))
      (node (ref "R25") (pin "2") (pinfunction "2_2") (pintype "passive"))
      (node (ref "R5") (pin "2") (pinfunction "2_2") (pintype "passive"))
      (node (ref "R6") (pin "2") (pinfunction "2_2") (pintype "passive"))
      (node (ref "S1") (pin "3") (pinfunction "3_3") (pintype "passive"))
      (node (ref "TK1") (pin "3") (pintype "passive"))
      (node (ref "TK2") (pin "3") (pintype "passive"))
      (node (ref "U1") (pin "1") (pinfunction "GND_1") (pintype "passive"))
      (node (ref "U2") (pin "1") (pinfunction "A0_1") (pintype "passive"))
      (node (ref "U2") (pin "2") (pinfunction "A1_2") (pintype "passive"))
      (node (ref "U2") (pin "3") (pinfunction "A2_3") (pintype "passive"))
      (node (ref "U2") (pin "4") (pinfunction "GND_4") (pintype "passive"))
      (node (ref "U2") (pin "7") (pinfunction "WP_7") (pintype "passive"))
      (node (ref "U3") (pin "23") (pinfunction "VSS_1_23") (pintype "power_in"))
      (node (ref "U3") (pin "35") (pinfunction "VSS_2_35") (pintype "power_in"))
      (node (ref "U3") (pin "47") (pinfunction "VSS_3_47") (pintype "power_in"))
      (node (ref "U3") (pin "8") (pinfunction "VSSA_8") (pintype "power_in"))
      (node (ref "U4") (pin "4") (pinfunction "GND_4") (pintype "power_in"))
      (node (ref "U5") (pin "3") (pinfunction "GND_3") (pintype "power_in"))
      (node (ref "U6") (pin "2") (pinfunction "GND_2") (pintype "passive"))
    )
    (net (code "58") (name "Net-(D1-A)") (class "Default")
      (node (ref "D1") (pin "1") (pinfunction "A_1") (pintype "passive"))
      (node (ref "R1") (pin "1") (pinfunction "1_1") (pintype "passive"))
    )
    (net (code "59") (name "Net-(D2-A)") (class "Default")
      (node (ref "D2") (pin "1") (pinfunction "A_1") (pintype "passive"))
      (node (ref "R2") (pin "2") (pinfunction "2_2") (pintype "passive"))
    )
    (net (code "60") (name "Net-(D3-A)") (class "Default")
      (node (ref "D3") (pin "1") (pinfunction "A_1") (pintype "passive"))
      (node (ref "R3") (pin "2") (pinfunction "2_2") (pintype "passive"))
    )
    (net (code "61") (name "Net-(F1-Pad1)") (class "Default")
      (node (ref "F1") (pin "1") (pinfunction "1_1") (pintype "passive"))
      (node (ref "S2") (pin "2") (pinfunction "2_2") (pintype "passive"))
    )
    (net (code "62") (name "Net-(P3-Pad2)") (class "Default")
      (node (ref "P3") (pin "2") (pinfunction "2_2") (pintype "passive"))
      (node (ref "R6") (pin "1") (pinfunction "1_1") (pintype "passive"))
    )
    (net (code "63") (name "Net-(P5-CD{slash}DAT3{slash}CS)") (class "Default")
      (node (ref "P5") (pin "2") (pinfunction "CD/DAT3/CS_2") (pintype "passive"))
      (node (ref "R13") (pin "1") (pintype "passive"))
      (node (ref "R14") (pin "1") (pinfunction "1_1") (pintype "passive"))
    )
    (net (code "64") (name "Net-(P5-DAT1{slash}RSV)") (class "Default")
      (node (ref "P5") (pin "8") (pinfunction "DAT1/RSV_8") (pintype "passive"))
      (node (ref "R15") (pin "2") (pinfunction "2_2") (pintype "passive"))
    )
    (net (code "65") (name "Net-(P5-DAT2{slash}RSV)") (class "Default")
      (node (ref "P5") (pin "1") (pinfunction "DAT2/RSV_1") (pintype "passive"))
      (node (ref "R12") (pin "1") (pinfunction "1_1") (pintype "passive"))
    )
    (net (code "66") (name "Net-(P12-CC-PadA5)") (class "Default")
      (node (ref "P12") (pin "A5") (pinfunction "CC_A5") (pintype "bidirectional"))
      (node (ref "R25") (pin "1") (pinfunction "1_1") (pintype "passive"))
    )
    (net (code "67") (name "Net-(P12-CC-PadB5)") (class "Default")
      (node (ref "P12") (pin "B5") (pinfunction "CC_B5") (pintype "bidirectional"))
      (node (ref "R24") (pin "1") (pinfunction "1_1") (pintype "passive"))
    )
    (net (code "68") (name "Net-(P_HUSB1-CC-PadA5)") (class "Default")
      (node (ref "P_HUSB1") (pin "A5") (pinfunction "CC_A5") (pintype "bidirectional"))
      (node (ref "R20") (pin "1") (pinfunction "1_1") (pintype "passive"))
    )
    (net (code "69") (name "Net-(P_HUSB1-CC-PadB5)") (class "Default")
      (node (ref "P_HUSB1") (pin "B5") (pinfunction "CC_B5") (pintype "bidirectional"))
      (node (ref "R21") (pin "1") (pinfunction "1_1") (pintype "passive"))
    )
    (net (code "70") (name "Net-(P_USB-CC-PadA5)") (class "Default")
      (node (ref "P_USB") (pin "A5") (pinfunction "CC_A5") (pintype "bidirectional"))
      (node (ref "R22") (pin "1") (pinfunction "1_1") (pintype "passive"))
    )
    (net (code "71") (name "Net-(P_USB-CC-PadB5)") (class "Default")
      (node (ref "P_USB") (pin "B5") (pinfunction "CC_B5") (pintype "bidirectional"))
      (node (ref "R23") (pin "1") (pinfunction "1_1") (pintype "passive"))
    )
    (net (code "72") (name "Net-(U4-CS#)") (class "Default")
      (node (ref "R10") (pin "1") (pintype "passive"))
      (node (ref "R11") (pin "1") (pinfunction "1_1") (pintype "passive"))
      (node (ref "U4") (pin "1") (pinfunction "CS#_1") (pintype "input"))
    )
    (net (code "73") (name "Net-(U6-RS)") (class "Default")
      (node (ref "R16") (pin "2") (pinfunction "2_2") (pintype "passive"))
      (node (ref "U6") (pin "8") (pinfunction "RS_8") (pintype "passive"))
    )
    (net (code "74") (name "unconnected-(P12-RFU1-PadA8)") (class "Default")
      (node (ref "P12") (pin "A8") (pinfunction "RFU1_A8") (pintype "bidirectional+no_connect"))
    )
    (net (code "75") (name "unconnected-(P12-RFU1-PadB8)") (class "Default")
      (node (ref "P12") (pin "B8") (pinfunction "RFU1_B8") (pintype "bidirectional+no_connect"))
    )
    (net (code "76") (name "unconnected-(P_HUSB1-RFU1-PadA8)") (class "Default")
      (node (ref "P_HUSB1") (pin "A8") (pinfunction "RFU1_A8") (pintype "bidirectional+no_connect"))
    )
    (net (code "77") (name "unconnected-(P_HUSB1-RFU1-PadB8)") (class "Default")
      (node (ref "P_HUSB1") (pin "B8") (pinfunction "RFU1_B8") (pintype "bidirectional+no_connect"))
    )
    (net (code "78") (name "unconnected-(P_USB-RFU1-PadA8)") (class "Default")
      (node (ref "P_USB") (pin "A8") (pinfunction "RFU1_A8") (pintype "bidirectional+no_connect"))
    )
    (net (code "79") (name "unconnected-(P_USB-RFU1-PadB8)") (class "Default")
      (node (ref "P_USB") (pin "B8") (pinfunction "RFU1_B8") (pintype "bidirectional+no_connect"))
    )
    (net (code "80") (name "unconnected-(S2-Pad3)") (class "Default")
      (node (ref "S2") (pin "3") (pinfunction "3_3") (pintype "passive"))
    )
    (net (code "81") (name "unconnected-(U5-CTS#-Pad5)") (class "Default")
      (node (ref "U5") (pin "5") (pinfunction "CTS#_5") (pintype "input"))
    )
    (net (code "82") (name "unconnected-(U6-Vref-Pad5)") (class "Default")
      (node (ref "U6") (pin "5") (pinfunction "Vref_5") (pintype "passive"))
    )
  )
)
